# Main_sheet.net
KiCad netlist of a schematic drawn in Altium Designer
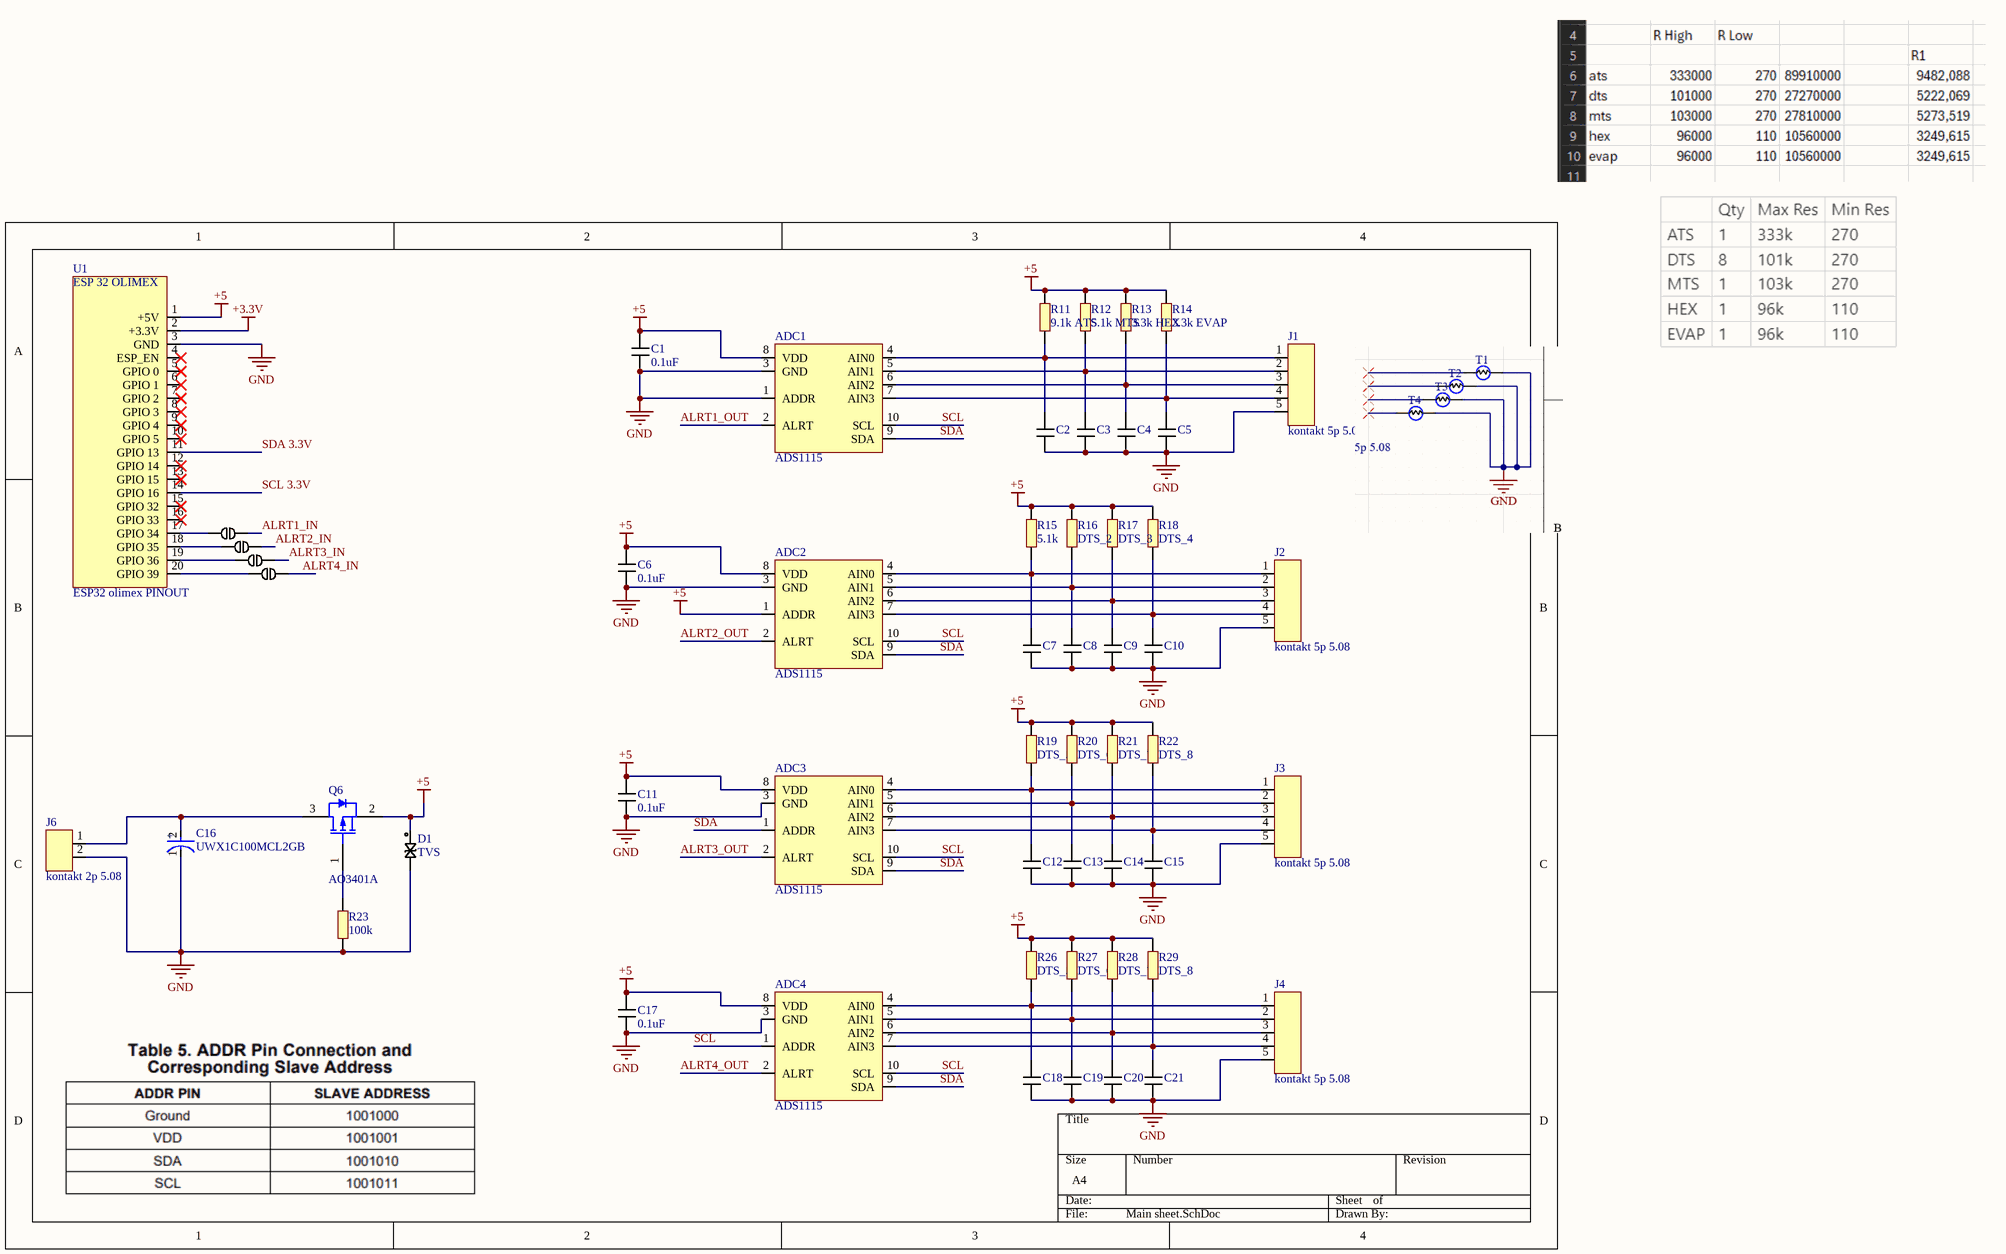
[diagram p0: Main sheet.SchDoc]

(export (version "E")
  (design (tool "Eeschema 10.0.6"))
  (components
    (comp (ref "ADC1")
      (value "ADS1115")
      (footprint "TSSOP50P490X110-10N ADS1115")
      (description "4-Channel Single ADC Delta-Sigma 860sps 16-bit Serial 10-Pin VSSOP T/R")
      (fields
        (field (name "MANUFACTURER") "Texas Instruments")
        (field (name "MANUFACTURER PART NUMBER") "ADS1115IDGSR")
      )
      (libsource (lib "Schlib1") (part "ADS1113"))
    )
    (comp (ref "ADC2")
      (value "ADS1115")
      (footprint "TSSOP50P490X110-10N ADS1115")
      (description "4-Channel Single ADC Delta-Sigma 860sps 16-bit Serial 10-Pin VSSOP T/R")
      (fields
        (field (name "MANUFACTURER") "Texas Instruments")
        (field (name "MANUFACTURER PART NUMBER") "ADS1115IDGSR")
      )
      (libsource (lib "Schlib1") (part "ADS1113"))
    )
    (comp (ref "ADC3")
      (value "ADS1115")
      (footprint "TSSOP50P490X110-10N ADS1115")
      (description "4-Channel Single ADC Delta-Sigma 860sps 16-bit Serial 10-Pin VSSOP T/R")
      (fields
        (field (name "MANUFACTURER") "Texas Instruments")
        (field (name "MANUFACTURER PART NUMBER") "ADS1115IDGSR")
      )
      (libsource (lib "Schlib1") (part "ADS1113"))
    )
    (comp (ref "ADC4")
      (value "ADS1115")
      (footprint "TSSOP50P490X110-10N ADS1115")
      (description "4-Channel Single ADC Delta-Sigma 860sps 16-bit Serial 10-Pin VSSOP T/R")
      (fields
        (field (name "MANUFACTURER") "Texas Instruments")
        (field (name "MANUFACTURER PART NUMBER") "ADS1115IDGSR")
      )
      (libsource (lib "Schlib1") (part "ADS1113"))
    )
    (comp (ref "C1")
      (value "0.1uF")
      (footprint "Cap 0603")
      (description "C14663")
      (libsource (lib "Schlib1") (part "C0603"))
    )
    (comp (ref "C2")
      (value "C0603")
      (footprint "Cap 0603")
      (description "C96446")
      (libsource (lib "Schlib1") (part "C0603"))
    )
    (comp (ref "C3")
      (value "C0603")
      (footprint "Cap 0603")
      (description "C96446")
      (libsource (lib "Schlib1") (part "C0603"))
    )
    (comp (ref "C4")
      (value "C0603")
      (footprint "Cap 0603")
      (description "C96446")
      (libsource (lib "Schlib1") (part "C0603"))
    )
    (comp (ref "C5")
      (value "C0603")
      (footprint "Cap 0603")
      (description "C96446")
      (libsource (lib "Schlib1") (part "C0603"))
    )
    (comp (ref "C6")
      (value "0.1uF")
      (footprint "Cap 0603")
      (description "C14663")
      (libsource (lib "Schlib1") (part "C0603"))
    )
    (comp (ref "C7")
      (value "C0603")
      (footprint "Cap 0603")
      (description "C96446")
      (libsource (lib "Schlib1") (part "C0603"))
    )
    (comp (ref "C8")
      (value "C0603")
      (footprint "Cap 0603")
      (description "C96446")
      (libsource (lib "Schlib1") (part "C0603"))
    )
    (comp (ref "C9")
      (value "C0603")
      (footprint "Cap 0603")
      (description "C96446")
      (libsource (lib "Schlib1") (part "C0603"))
    )
    (comp (ref "C10")
      (value "C0603")
      (footprint "Cap 0603")
      (description "C96446")
      (libsource (lib "Schlib1") (part "C0603"))
    )
    (comp (ref "C11")
      (value "0.1uF")
      (footprint "Cap 0603")
      (description "C14663")
      (libsource (lib "Schlib1") (part "C0603"))
    )
    (comp (ref "C12")
      (value "10uf")
      (footprint "Cap 0603")
      (description "C96446")
      (libsource (lib "Schlib1") (part "C0603"))
    )
    (comp (ref "C13")
      (value "C0603")
      (footprint "Cap 0603")
      (description "C96446")
      (libsource (lib "Schlib1") (part "C0603"))
    )
    (comp (ref "C14")
      (value "C0603")
      (footprint "Cap 0603")
      (description "C96446")
      (libsource (lib "Schlib1") (part "C0603"))
    )
    (comp (ref "C15")
      (value "C0603")
      (footprint "Cap 0603")
      (description "C96446")
      (libsource (lib "Schlib1") (part "C0603"))
    )
    (comp (ref "C16")
      (value "UWX1C100MCL2GB")
      (footprint "FP-UWX1C100MCL2GB-MFG")
      (description "UWX1C100MCL2GB WX Series 10 uF 16 V 85°C Ø3 x 5.4 mm SMT Chip Aluminum Electrolytic Cap")
      (fields (field (name "TOLERANCE") "20%") (field (name "VOLTAGE") "16V"))
      (libsource (lib "Altium Content Vault") (part "cf48714ba7e38822c1575c7ec0b6d1f"))
    )
    (comp (ref "C17")
      (value "0.1uF")
      (footprint "Cap 0603")
      (description "C14663")
      (libsource (lib "Schlib1") (part "C0603"))
    )
    (comp (ref "C18")
      (value "10uf")
      (footprint "Cap 0603")
      (description "C96446")
      (libsource (lib "Schlib1") (part "C0603"))
    )
    (comp (ref "C19")
      (value "C0603")
      (footprint "Cap 0603")
      (description "C96446")
      (libsource (lib "Schlib1") (part "C0603"))
    )
    (comp (ref "C20")
      (value "C0603")
      (footprint "Cap 0603")
      (description "C96446")
      (libsource (lib "Schlib1") (part "C0603"))
    )
    (comp (ref "C21")
      (value "C0603")
      (footprint "Cap 0603")
      (description "C96446")
      (libsource (lib "Schlib1") (part "C0603"))
    )
    (comp (ref "D1")
      (value "TVS")
      (footprint "DO-214AA P6SMB")
      (description "jlc: C78395")
      (fields
        (field (name "MANUFACTURER PART NUMBER") "P6SMB6.8CA/TR13")
        (field (name "MANUFACTURER") "Brightking")
      )
      (libsource (lib "Schlib1") (part "TVS"))
    )
    (comp (ref "J1")
      (value "kontakt 5p 5.08")
      (footprint "Kontakt 5P 3.5")
      (libsource (lib "Schlib1") (part "kontakt 5p 5.08"))
    )
    (comp (ref "J2")
      (value "kontakt 5p 5.08")
      (footprint "Kontakt 5P 3.5")
      (libsource (lib "Schlib1") (part "kontakt 5p 5.08"))
    )
    (comp (ref "J3")
      (value "kontakt 5p 5.08")
      (footprint "Kontakt 5P 3.5")
      (libsource (lib "Schlib1") (part "kontakt 5p 5.08"))
    )
    (comp (ref "J4")
      (value "kontakt 5p 5.08")
      (footprint "Kontakt 5P 3.5")
      (libsource (lib "Schlib1") (part "kontakt 5p 5.08"))
    )
    (comp (ref "J6")
      (value "kontakt 2p 5.08")
      (footprint "Kontakt 2P 5.08")
      (libsource (lib "Schlib1") (part "kontakt 2p 5.08"))
    )
    (comp (ref "JUMP1")
      (value "Solder jumper")
      (footprint "jumper")
      (libsource (lib "Schlib1") (part "Solder jumper"))
    )
    (comp (ref "JUMP2")
      (value "Solder jumper")
      (footprint "jumper")
      (libsource (lib "Schlib1") (part "Solder jumper"))
    )
    (comp (ref "JUMP3")
      (value "Solder jumper")
      (footprint "jumper")
      (libsource (lib "Schlib1") (part "Solder jumper"))
    )
    (comp (ref "JUMP4")
      (value "Solder jumper")
      (footprint "jumper")
      (libsource (lib "Schlib1") (part "Solder jumper"))
    )
    (comp (ref "Q6")
      (value "AO3401A")
      (footprint "AO-SOT-23-3L_V")
      (description "P-Channel MOSFET, 30 V, 4 A, -55 to 150 degC, 3-Pin SOT-23-3L, RoHS, Tape and Reel")
      (fields (field (name "MANUFACTURER") "Alpha and Omega"))
      (libsource (lib "Altium Content Vault") (part "PEMOS-GSD-3"))
    )
    (comp (ref "R11")
      (value "9.1k ATS")
      (footprint "Res 0603")
      (description "ATS\r\nThermistor: 270-333k\r\nR11: 9.1k")
      (libsource (lib "Schlib1") (part "R0603"))
    )
    (comp (ref "R12")
      (value "5.1k MTS")
      (footprint "Res 0603")
      (description "MTS\r\nThermistor: 103k\r\nR12: 5.1k")
      (libsource (lib "Schlib1") (part "R0603"))
    )
    (comp (ref "R13")
      (value "3.3k HEX")
      (footprint "Res 0603")
      (description "HEX\r\nThermistor: 96k\r\nR13: 3.3k")
      (libsource (lib "Schlib1") (part "R0603"))
    )
    (comp (ref "R14")
      (value "3.3k EVAP")
      (footprint "Res 0603")
      (description "EVAP\r\nThermistor: 96k\r\nR14: 3.3k")
      (libsource (lib "Schlib1") (part "R0603"))
    )
    (comp (ref "R15")
      (value "5.1k")
      (footprint "Res 0603")
      (description "DTS_1\r\nThermistor: 101k\r\nR15: 5.1k")
      (libsource (lib "Schlib1") (part "R0603"))
    )
    (comp (ref "R16")
      (value "DTS_2")
      (footprint "Res 0603")
      (description "DTS_2\r\nThermistor: 101k\r\nR16: 5.1k")
      (libsource (lib "Schlib1") (part "R0603"))
    )
    (comp (ref "R17")
      (value "DTS_3")
      (footprint "Res 0603")
      (description "DTS_3\r\nThermistor: 101k\r\nR17: 5.1k")
      (libsource (lib "Schlib1") (part "R0603"))
    )
    (comp (ref "R18")
      (value "DTS_4")
      (footprint "Res 0603")
      (description "DTS_4\r\nThermistor: 101k\r\nR18: 5.1k")
      (libsource (lib "Schlib1") (part "R0603"))
    )
    (comp (ref "R19")
      (value "DTS_5")
      (footprint "Res 0603")
      (description "DTS_5\r\nThermistor: 101k\r\nR19: 5.1k")
      (libsource (lib "Schlib1") (part "R0603"))
    )
    (comp (ref "R20")
      (value "DTS_6")
      (footprint "Res 0603")
      (description "DTS_6\r\nThermistor: 101k\r\nR20: 5.1k")
      (libsource (lib "Schlib1") (part "R0603"))
    )
    (comp (ref "R21")
      (value "DTS_7")
      (footprint "Res 0603")
      (description "DTS_7\r\nThermistor: 101k\r\nR21: 5.1k")
      (libsource (lib "Schlib1") (part "R0603"))
    )
    (comp (ref "R22")
      (value "DTS_8")
      (footprint "Res 0603")
      (description "DTS_8\r\nThermistor: 101k\r\nR22: 5.1k")
      (libsource (lib "Schlib1") (part "R0603"))
    )
    (comp (ref "R23") (value "100k") (footprint "Res 0603") (libsource (lib "Schlib1") (part "R0603")))
    (comp (ref "R26")
      (value "DTS_5")
      (footprint "Res 0603")
      (description "DTS_5\r\nThermistor: 101k\r\nR19: 5.1k")
      (libsource (lib "Schlib1") (part "R0603"))
    )
    (comp (ref "R27")
      (value "DTS_6")
      (footprint "Res 0603")
      (description "DTS_6\r\nThermistor: 101k\r\nR20: 5.1k")
      (libsource (lib "Schlib1") (part "R0603"))
    )
    (comp (ref "R28")
      (value "DTS_7")
      (footprint "Res 0603")
      (description "DTS_7\r\nThermistor: 101k\r\nR21: 5.1k")
      (libsource (lib "Schlib1") (part "R0603"))
    )
    (comp (ref "R29")
      (value "DTS_8")
      (footprint "Res 0603")
      (description "DTS_8\r\nThermistor: 101k\r\nR22: 5.1k")
      (libsource (lib "Schlib1") (part "R0603"))
    )
    (comp (ref "U1")
      (value "ESP32 olimex PINOUT")
      (footprint "ESP32 OLIMEX POE")
      (libsource (lib "Schlib1") (part "ESP32 olimex PINOUT"))
    )
  )
  (nets
    (net (code "1") (name "+3.3V") (class "Default")
      (node (ref "U1") (pin "2") (pinfunction "+3.3V_2") (pintype "passive"))
    )
    (net (code "2") (name "+5") (class "Default")
      (node (ref "ADC1") (pin "8") (pinfunction "VDD_8") (pintype "passive"))
      (node (ref "ADC2") (pin "1") (pinfunction "ADDR_1") (pintype "passive"))
      (node (ref "ADC2") (pin "8") (pinfunction "VDD_8") (pintype "passive"))
      (node (ref "ADC3") (pin "8") (pinfunction "VDD_8") (pintype "passive"))
      (node (ref "ADC4") (pin "8") (pinfunction "VDD_8") (pintype "passive"))
      (node (ref "C1") (pin "2") (pinfunction "2_2") (pintype "passive"))
      (node (ref "C11") (pin "2") (pinfunction "2_2") (pintype "passive"))
      (node (ref "C17") (pin "2") (pinfunction "2_2") (pintype "passive"))
      (node (ref "C6") (pin "2") (pinfunction "2_2") (pintype "passive"))
      (node (ref "D1") (pin "1") (pinfunction "1_1") (pintype "passive"))
      (node (ref "Q6") (pin "2") (pinfunction "SOURCE_2") (pintype "passive"))
      (node (ref "R11") (pin "2") (pinfunction "2_2") (pintype "passive"))
      (node (ref "R12") (pin "2") (pinfunction "2_2") (pintype "passive"))
      (node (ref "R13") (pin "2") (pinfunction "2_2") (pintype "passive"))
      (node (ref "R14") (pin "2") (pinfunction "2_2") (pintype "passive"))
      (node (ref "R15") (pin "2") (pinfunction "2_2") (pintype "passive"))
      (node (ref "R16") (pin "2") (pinfunction "2_2") (pintype "passive"))
      (node (ref "R17") (pin "2") (pinfunction "2_2") (pintype "passive"))
      (node (ref "R18") (pin "2") (pinfunction "2_2") (pintype "passive"))
      (node (ref "R19") (pin "2") (pinfunction "2_2") (pintype "passive"))
      (node (ref "R20") (pin "2") (pinfunction "2_2") (pintype "passive"))
      (node (ref "R21") (pin "2") (pinfunction "2_2") (pintype "passive"))
      (node (ref "R22") (pin "2") (pinfunction "2_2") (pintype "passive"))
      (node (ref "R26") (pin "2") (pinfunction "2_2") (pintype "passive"))
      (node (ref "R27") (pin "2") (pinfunction "2_2") (pintype "passive"))
      (node (ref "R28") (pin "2") (pinfunction "2_2") (pintype "passive"))
      (node (ref "R29") (pin "2") (pinfunction "2_2") (pintype "passive"))
      (node (ref "U1") (pin "1") (pinfunction "+5V_1") (pintype "passive"))
    )
    (net (code "3") (name "/ALRT1_IN") (class "Default")
      (node (ref "JUMP4") (pin "2") (pinfunction "2_2") (pintype "passive"))
    )
    (net (code "4") (name "/ALRT1_OUT") (class "Default")
      (node (ref "ADC1") (pin "2") (pinfunction "ALRT_2") (pintype "passive"))
    )
    (net (code "5") (name "/ALRT2_IN") (class "Default")
      (node (ref "JUMP1") (pin "2") (pinfunction "2_2") (pintype "passive"))
    )
    (net (code "6") (name "/ALRT2_OUT") (class "Default")
      (node (ref "ADC2") (pin "2") (pinfunction "ALRT_2") (pintype "passive"))
    )
    (net (code "7") (name "/ALRT3_IN") (class "Default")
      (node (ref "JUMP2") (pin "2") (pinfunction "2_2") (pintype "passive"))
    )
    (net (code "8") (name "/ALRT3_OUT") (class "Default")
      (node (ref "ADC3") (pin "2") (pinfunction "ALRT_2") (pintype "passive"))
    )
    (net (code "9") (name "/ALRT4_IN") (class "Default")
      (node (ref "JUMP3") (pin "2") (pinfunction "2_2") (pintype "passive"))
    )
    (net (code "10") (name "/ALRT4_OUT") (class "Default")
      (node (ref "ADC4") (pin "2") (pinfunction "ALRT_2") (pintype "passive"))
    )
    (net (code "11") (name "/SCL") (class "Default")
      (node (ref "ADC1") (pin "10") (pinfunction "SCL_10") (pintype "passive"))
      (node (ref "ADC2") (pin "10") (pinfunction "SCL_10") (pintype "passive"))
      (node (ref "ADC3") (pin "10") (pinfunction "SCL_10") (pintype "passive"))
      (node (ref "ADC4") (pin "1") (pinfunction "ADDR_1") (pintype "passive"))
      (node (ref "ADC4") (pin "10") (pinfunction "SCL_10") (pintype "passive"))
    )
    (net (code "12") (name "/SCL 3.3V") (class "Default")
      (node (ref "U1") (pin "14") (pinfunction "GPIO_16_14") (pintype "passive"))
    )
    (net (code "13") (name "/SDA") (class "Default")
      (node (ref "ADC1") (pin "9") (pinfunction "SDA_9") (pintype "passive"))
      (node (ref "ADC2") (pin "9") (pinfunction "SDA_9") (pintype "passive"))
      (node (ref "ADC3") (pin "1") (pinfunction "ADDR_1") (pintype "passive"))
      (node (ref "ADC3") (pin "9") (pinfunction "SDA_9") (pintype "passive"))
      (node (ref "ADC4") (pin "9") (pinfunction "SDA_9") (pintype "passive"))
    )
    (net (code "14") (name "/SDA 3.3V") (class "Default")
      (node (ref "U1") (pin "11") (pinfunction "GPIO_13_11") (pintype "passive"))
    )
    (net (code "15") (name "GND") (class "Default")
      (node (ref "ADC1") (pin "1") (pinfunction "ADDR_1") (pintype "passive"))
      (node (ref "ADC1") (pin "3") (pinfunction "GND_3") (pintype "passive"))
      (node (ref "ADC2") (pin "3") (pinfunction "GND_3") (pintype "passive"))
      (node (ref "ADC3") (pin "3") (pinfunction "GND_3") (pintype "passive"))
      (node (ref "ADC4") (pin "3") (pinfunction "GND_3") (pintype "passive"))
      (node (ref "C1") (pin "1") (pinfunction "1_1") (pintype "passive"))
      (node (ref "C10") (pin "1") (pinfunction "1_1") (pintype "passive"))
      (node (ref "C11") (pin "1") (pinfunction "1_1") (pintype "passive"))
      (node (ref "C12") (pin "1") (pinfunction "1_1") (pintype "passive"))
      (node (ref "C13") (pin "1") (pinfunction "1_1") (pintype "passive"))
      (node (ref "C14") (pin "1") (pinfunction "1_1") (pintype "passive"))
      (node (ref "C15") (pin "1") (pinfunction "1_1") (pintype "passive"))
      (node (ref "C16") (pin "1") (pinfunction "C_1") (pintype "passive"))
      (node (ref "C17") (pin "1") (pinfunction "1_1") (pintype "passive"))
      (node (ref "C18") (pin "1") (pinfunction "1_1") (pintype "passive"))
      (node (ref "C19") (pin "1") (pinfunction "1_1") (pintype "passive"))
      (node (ref "C2") (pin "1") (pinfunction "1_1") (pintype "passive"))
      (node (ref "C20") (pin "1") (pinfunction "1_1") (pintype "passive"))
      (node (ref "C21") (pin "1") (pinfunction "1_1") (pintype "passive"))
      (node (ref "C3") (pin "1") (pinfunction "1_1") (pintype "passive"))
      (node (ref "C4") (pin "1") (pinfunction "1_1") (pintype "passive"))
      (node (ref "C5") (pin "1") (pinfunction "1_1") (pintype "passive"))
      (node (ref "C6") (pin "1") (pinfunction "1_1") (pintype "passive"))
      (node (ref "C7") (pin "1") (pinfunction "1_1") (pintype "passive"))
      (node (ref "C8") (pin "1") (pinfunction "1_1") (pintype "passive"))
      (node (ref "C9") (pin "1") (pinfunction "1_1") (pintype "passive"))
      (node (ref "D1") (pin "2") (pinfunction "2_2") (pintype "passive"))
      (node (ref "J1") (pin "5") (pinfunction "5_5") (pintype "passive"))
      (node (ref "J2") (pin "5") (pinfunction "5_5") (pintype "passive"))
      (node (ref "J3") (pin "5") (pinfunction "5_5") (pintype "passive"))
      (node (ref "J4") (pin "5") (pinfunction "5_5") (pintype "passive"))
      (node (ref "J6") (pin "2") (pinfunction "2_2") (pintype "passive"))
      (node (ref "R23") (pin "1") (pinfunction "1_1") (pintype "passive"))
      (node (ref "U1") (pin "3") (pinfunction "GND_3") (pintype "passive"))
    )
    (net (code "16") (name "Net-(ADC1-AIN0)") (class "Default")
      (node (ref "ADC1") (pin "4") (pinfunction "AIN0_4") (pintype "passive"))
      (node (ref "C2") (pin "2") (pinfunction "2_2") (pintype "passive"))
      (node (ref "J1") (pin "1") (pinfunction "1_1") (pintype "passive"))
      (node (ref "R11") (pin "1") (pinfunction "1_1") (pintype "passive"))
    )
    (net (code "17") (name "Net-(ADC1-AIN1)") (class "Default")
      (node (ref "ADC1") (pin "5") (pinfunction "AIN1_5") (pintype "passive"))
      (node (ref "C3") (pin "2") (pinfunction "2_2") (pintype "passive"))
      (node (ref "J1") (pin "2") (pinfunction "2_2") (pintype "passive"))
      (node (ref "R12") (pin "1") (pinfunction "1_1") (pintype "passive"))
    )
    (net (code "18") (name "Net-(ADC1-AIN2)") (class "Default")
      (node (ref "ADC1") (pin "6") (pinfunction "AIN2_6") (pintype "passive"))
      (node (ref "C4") (pin "2") (pinfunction "2_2") (pintype "passive"))
      (node (ref "J1") (pin "3") (pinfunction "3_3") (pintype "passive"))
      (node (ref "R13") (pin "1") (pinfunction "1_1") (pintype "passive"))
    )
    (net (code "19") (name "Net-(ADC1-AIN3)") (class "Default")
      (node (ref "ADC1") (pin "7") (pinfunction "AIN3_7") (pintype "passive"))
      (node (ref "C5") (pin "2") (pinfunction "2_2") (pintype "passive"))
      (node (ref "J1") (pin "4") (pinfunction "4_4") (pintype "passive"))
      (node (ref "R14") (pin "1") (pinfunction "1_1") (pintype "passive"))
    )
    (net (code "20") (name "Net-(ADC2-AIN0)") (class "Default")
      (node (ref "ADC2") (pin "4") (pinfunction "AIN0_4") (pintype "passive"))
      (node (ref "C7") (pin "2") (pinfunction "2_2") (pintype "passive"))
      (node (ref "J2") (pin "1") (pinfunction "1_1") (pintype "passive"))
      (node (ref "R15") (pin "1") (pinfunction "1_1") (pintype "passive"))
    )
    (net (code "21") (name "Net-(ADC2-AIN1)") (class "Default")
      (node (ref "ADC2") (pin "5") (pinfunction "AIN1_5") (pintype "passive"))
      (node (ref "C8") (pin "2") (pinfunction "2_2") (pintype "passive"))
      (node (ref "J2") (pin "2") (pinfunction "2_2") (pintype "passive"))
      (node (ref "R16") (pin "1") (pinfunction "1_1") (pintype "passive"))
    )
    (net (code "22") (name "Net-(ADC2-AIN2)") (class "Default")
      (node (ref "ADC2") (pin "6") (pinfunction "AIN2_6") (pintype "passive"))
      (node (ref "C9") (pin "2") (pinfunction "2_2") (pintype "passive"))
      (node (ref "J2") (pin "3") (pinfunction "3_3") (pintype "passive"))
      (node (ref "R17") (pin "1") (pinfunction "1_1") (pintype "passive"))
    )
    (net (code "23") (name "Net-(ADC2-AIN3)") (class "Default")
      (node (ref "ADC2") (pin "7") (pinfunction "AIN3_7") (pintype "passive"))
      (node (ref "C10") (pin "2") (pinfunction "2_2") (pintype "passive"))
      (node (ref "J2") (pin "4") (pinfunction "4_4") (pintype "passive"))
      (node (ref "R18") (pin "1") (pinfunction "1_1") (pintype "passive"))
    )
    (net (code "24") (name "Net-(ADC3-AIN0)") (class "Default")
      (node (ref "ADC3") (pin "4") (pinfunction "AIN0_4") (pintype "passive"))
      (node (ref "C12") (pin "2") (pinfunction "2_2") (pintype "passive"))
      (node (ref "J3") (pin "1") (pinfunction "1_1") (pintype "passive"))
      (node (ref "R19") (pin "1") (pinfunction "1_1") (pintype "passive"))
    )
    (net (code "25") (name "Net-(ADC3-AIN1)") (class "Default")
      (node (ref "ADC3") (pin "5") (pinfunction "AIN1_5") (pintype "passive"))
      (node (ref "C13") (pin "2") (pinfunction "2_2") (pintype "passive"))
      (node (ref "J3") (pin "2") (pinfunction "2_2") (pintype "passive"))
      (node (ref "R20") (pin "1") (pinfunction "1_1") (pintype "passive"))
    )
    (net (code "26") (name "Net-(ADC3-AIN2)") (class "Default")
      (node (ref "ADC3") (pin "6") (pinfunction "AIN2_6") (pintype "passive"))
      (node (ref "C14") (pin "2") (pinfunction "2_2") (pintype "passive"))
      (node (ref "J3") (pin "3") (pinfunction "3_3") (pintype "passive"))
      (node (ref "R21") (pin "1") (pinfunction "1_1") (pintype "passive"))
    )
    (net (code "27") (name "Net-(ADC3-AIN3)") (class "Default")
      (node (ref "ADC3") (pin "7") (pinfunction "AIN3_7") (pintype "passive"))
      (node (ref "C15") (pin "2") (pinfunction "2_2") (pintype "passive"))
      (node (ref "J3") (pin "4") (pinfunction "4_4") (pintype "passive"))
      (node (ref "R22") (pin "1") (pinfunction "1_1") (pintype "passive"))
    )
    (net (code "28") (name "Net-(ADC4-AIN0)") (class "Default")
      (node (ref "ADC4") (pin "4") (pinfunction "AIN0_4") (pintype "passive"))
      (node (ref "C18") (pin "2") (pinfunction "2_2") (pintype "passive"))
      (node (ref "J4") (pin "1") (pinfunction "1_1") (pintype "passive"))
      (node (ref "R26") (pin "1") (pinfunction "1_1") (pintype "passive"))
    )
    (net (code "29") (name "Net-(ADC4-AIN1)") (class "Default")
      (node (ref "ADC4") (pin "5") (pinfunction "AIN1_5") (pintype "passive"))
      (node (ref "C19") (pin "2") (pinfunction "2_2") (pintype "passive"))
      (node (ref "J4") (pin "2") (pinfunction "2_2") (pintype "passive"))
      (node (ref "R27") (pin "1") (pinfunction "1_1") (pintype "passive"))
    )
    (net (code "30") (name "Net-(ADC4-AIN2)") (class "Default")
      (node (ref "ADC4") (pin "6") (pinfunction "AIN2_6") (pintype "passive"))
      (node (ref "C20") (pin "2") (pinfunction "2_2") (pintype "passive"))
      (node (ref "J4") (pin "3") (pinfunction "3_3") (pintype "passive"))
      (node (ref "R28") (pin "1") (pinfunction "1_1") (pintype "passive"))
    )
    (net (code "31") (name "Net-(ADC4-AIN3)") (class "Default")
      (node (ref "ADC4") (pin "7") (pinfunction "AIN3_7") (pintype "passive"))
      (node (ref "C21") (pin "2") (pinfunction "2_2") (pintype "passive"))
      (node (ref "J4") (pin "4") (pinfunction "4_4") (pintype "passive"))
      (node (ref "R29") (pin "1") (pinfunction "1_1") (pintype "passive"))
    )
    (net (code "32") (name "Net-(C16-A)") (class "Default")
      (node (ref "C16") (pin "2") (pinfunction "A_2") (pintype "passive"))
      (node (ref "J6") (pin "1") (pinfunction "1_1") (pintype "passive"))
      (node (ref "Q6") (pin "3") (pinfunction "DRAIN_3") (pintype "passive"))
    )
    (net (code "33") (name "Net-(Q6-GATE)") (class "Default")
      (node (ref "Q6") (pin "1") (pinfunction "GATE_1") (pintype "passive"))
      (node (ref "R23") (pin "2") (pinfunction "2_2") (pintype "passive"))
    )
    (net (code "34") (name "Net-(U1-GPIO_34)") (class "Default")
      (node (ref "JUMP4") (pin "1") (pinfunction "1_1") (pintype "passive"))
      (node (ref "U1") (pin "17") (pinfunction "GPIO_34_17") (pintype "passive"))
    )
    (net (code "35") (name "Net-(U1-GPIO_35)") (class "Default")
      (node (ref "JUMP1") (pin "1") (pinfunction "1_1") (pintype "passive"))
      (node (ref "U1") (pin "18") (pinfunction "GPIO_35_18") (pintype "passive"))
    )
    (net (code "36") (name "Net-(U1-GPIO_36)") (class "Default")
      (node (ref "JUMP2") (pin "1") (pinfunction "1_1") (pintype "passive"))
      (node (ref "U1") (pin "19") (pinfunction "GPIO_36_19") (pintype "passive"))
    )
    (net (code "37") (name "Net-(U1-GPIO_39)") (class "Default")
      (node (ref "JUMP3") (pin "1") (pinfunction "1_1") (pintype "passive"))
      (node (ref "U1") (pin "20") (pinfunction "GPIO_39_20") (pintype "passive"))
    )
    (net (code "38") (name "unconnected-(U1-ESP_EN-Pad4)") (class "Default")
      (node (ref "U1") (pin "4") (pinfunction "ESP_EN_4") (pintype "passive+no_connect"))
    )
    (net (code "39") (name "unconnected-(U1-GPIO_0-Pad5)") (class "Default")
      (node (ref "U1") (pin "5") (pinfunction "GPIO_0_5") (pintype "passive+no_connect"))
    )
    (net (code "40") (name "unconnected-(U1-GPIO_1-Pad6)") (class "Default")
      (node (ref "U1") (pin "6") (pinfunction "GPIO_1_6") (pintype "passive+no_connect"))
    )
    (net (code "41") (name "unconnected-(U1-GPIO_2-Pad7)") (class "Default")
      (node (ref "U1") (pin "7") (pinfunction "GPIO_2_7") (pintype "passive+no_connect"))
    )
    (net (code "42") (name "unconnected-(U1-GPIO_3-Pad8)") (class "Default")
      (node (ref "U1") (pin "8") (pinfunction "GPIO_3_8") (pintype "passive+no_connect"))
    )
    (net (code "43") (name "unconnected-(U1-GPIO_4-Pad9)") (class "Default")
      (node (ref "U1") (pin "9") (pinfunction "GPIO_4_9") (pintype "passive+no_connect"))
    )
    (net (code "44") (name "unconnected-(U1-GPIO_5-Pad10)") (class "Default")
      (node (ref "U1") (pin "10") (pinfunction "GPIO_5_10") (pintype "passive+no_connect"))
    )
    (net (code "45") (name "unconnected-(U1-GPIO_14-Pad12)") (class "Default")
      (node (ref "U1") (pin "12") (pinfunction "GPIO_14_12") (pintype "passive+no_connect"))
    )
    (net (code "46") (name "unconnected-(U1-GPIO_15-Pad13)") (class "Default")
      (node (ref "U1") (pin "13") (pinfunction "GPIO_15_13") (pintype "passive+no_connect"))
    )
    (net (code "47") (name "unconnected-(U1-GPIO_32-Pad15)") (class "Default")
      (node (ref "U1") (pin "15") (pinfunction "GPIO_32_15") (pintype "passive+no_connect"))
    )
    (net (code "48") (name "unconnected-(U1-GPIO_33-Pad16)") (class "Default")
      (node (ref "U1") (pin "16") (pinfunction "GPIO_33_16") (pintype "passive+no_connect"))
    )
  )
)
